# Microcontroller.net
KiCad netlist of a schematic drawn in Altium Designer
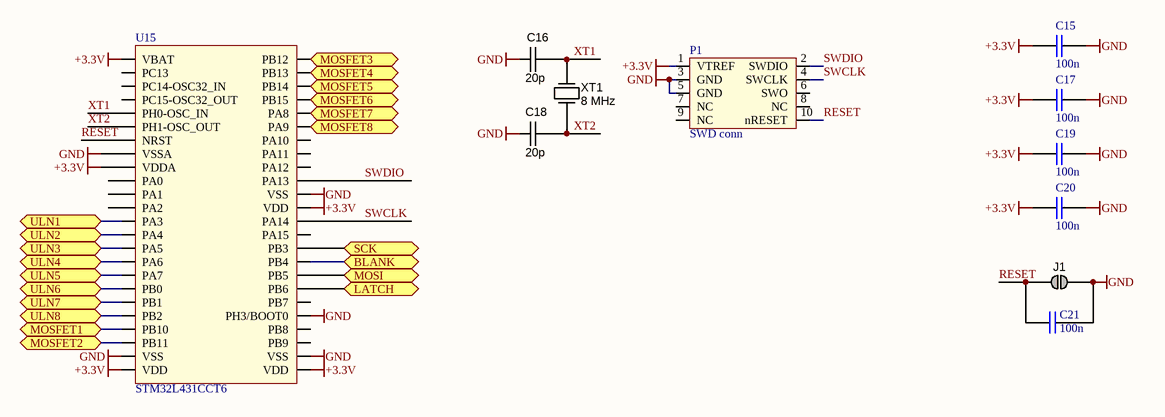
[diagram p0: Microcontroller.SchDoc]

(export (version "E")
  (design (tool "Eeschema 10.0.6"))
  (components
    (comp (ref "C15")
      (value "100n")
      (footprint "Cap 0603")
      (description "Capacitor 100nF 50V 0603 SMD")
      (libsource (lib "Komponente") (part "Cap 100nF 50V 0603 SMD"))
    )
    (comp (ref "C16")
      (value "20p")
      (footprint "CAPC2012X135N")
      (description "Capacitor SMD Cer 100nF 10% 50V X7R 0805")
      (fields (field (name "TOLERANCE") "±10%") (field (name "Comment") "approved sub OK"))
      (libsource (lib "PBL - Capacitors") (part "CAPC_100n_0805_X7R_50V_10%"))
    )
    (comp (ref "C17")
      (value "100n")
      (footprint "Cap 0603")
      (description "Capacitor 100nF 50V 0603 SMD")
      (libsource (lib "Komponente") (part "Cap 100nF 50V 0603 SMD"))
    )
    (comp (ref "C18")
      (value "20p")
      (footprint "CAPC2012X135N")
      (description "Capacitor SMD Cer 100nF 10% 50V X7R 0805")
      (fields (field (name "TOLERANCE") "±10%") (field (name "Comment") "approved sub OK"))
      (libsource (lib "PBL - Capacitors") (part "CAPC_100n_0805_X7R_50V_10%"))
    )
    (comp (ref "C19")
      (value "100n")
      (footprint "Cap 0603")
      (description "Capacitor 100nF 50V 0603 SMD")
      (libsource (lib "Komponente") (part "Cap 100nF 50V 0603 SMD"))
    )
    (comp (ref "C20")
      (value "100n")
      (footprint "Cap 0603")
      (description "Capacitor 100nF 50V 0603 SMD")
      (libsource (lib "Komponente") (part "Cap 100nF 50V 0603 SMD"))
    )
    (comp (ref "C21")
      (value "100n")
      (footprint "Cap 0603")
      (description "Capacitor 100nF 50V 0603 SMD")
      (libsource (lib "Komponente") (part "Cap 100nF 50V 0603 SMD"))
    )
    (comp (ref "J1")
      (value "Jumper")
      (footprint "HDR1X2")
      (description "SMD jumper")
      (libsource (lib "PBL - Pads and Jumpers") (part "JUMP1"))
    )
    (comp (ref "P1")
      (value "SWD conn")
      (footprint "SWD connector")
      (description "SWD connector")
      (libsource (lib "AltiumLibrary") (part "SW_debug"))
    )
    (comp (ref "U15")
      (value "STM32L431CCT6")
      (footprint "STM-LQFP48")
      (description "STM32 L4")
      (libsource (lib "Lib_darijo") (part "STM32L431CCT6"))
    )
    (comp (ref "XT1")
      (value "8 MHz")
      (footprint "CRYSTAL_HC49-US-SM")
      (description "Resonator Ceramic 6.00 MHz 30ppm")
      (libsource (lib "PBL - Resonators") (part "Crystal_6MHz_HC49/US"))
    )
  )
  (nets
    (net (code "1") (name "+3.3V") (class "Default")
      (node (ref "C15") (pin "1") (pinfunction "1_1") (pintype "passive"))
      (node (ref "C17") (pin "1") (pinfunction "1_1") (pintype "passive"))
      (node (ref "C19") (pin "1") (pinfunction "1_1") (pintype "passive"))
      (node (ref "C20") (pin "1") (pinfunction "1_1") (pintype "passive"))
      (node (ref "P1") (pin "1") (pinfunction "VTREF_1") (pintype "passive"))
      (node (ref "U15") (pin "1") (pinfunction "VBAT_1") (pintype "passive"))
      (node (ref "U15") (pin "24") (pinfunction "VDD_24") (pintype "passive"))
      (node (ref "U15") (pin "36") (pinfunction "VDD_36") (pintype "passive"))
      (node (ref "U15") (pin "48") (pinfunction "VDD_48") (pintype "passive"))
      (node (ref "U15") (pin "9") (pinfunction "VDDA_9") (pintype "passive"))
    )
    (net (code "2") (name "/BLANK") (class "Default")
      (node (ref "U15") (pin "40") (pinfunction "PB4_40") (pintype "passive"))
    )
    (net (code "3") (name "/LATCH") (class "Default")
      (node (ref "U15") (pin "42") (pinfunction "PB6_42") (pintype "passive"))
    )
    (net (code "4") (name "/MOSFET1") (class "Default")
      (node (ref "U15") (pin "21") (pinfunction "PB10_21") (pintype "passive"))
    )
    (net (code "5") (name "/MOSFET2") (class "Default")
      (node (ref "U15") (pin "22") (pinfunction "PB11_22") (pintype "passive"))
    )
    (net (code "6") (name "/MOSFET3") (class "Default")
      (node (ref "U15") (pin "25") (pinfunction "PB12_25") (pintype "passive"))
    )
    (net (code "7") (name "/MOSFET4") (class "Default")
      (node (ref "U15") (pin "26") (pinfunction "PB13_26") (pintype "passive"))
    )
    (net (code "8") (name "/MOSFET5") (class "Default")
      (node (ref "U15") (pin "27") (pinfunction "PB14_27") (pintype "passive"))
    )
    (net (code "9") (name "/MOSFET6") (class "Default")
      (node (ref "U15") (pin "28") (pinfunction "PB15_28") (pintype "passive"))
    )
    (net (code "10") (name "/MOSFET7") (class "Default")
      (node (ref "U15") (pin "29") (pinfunction "PA8_29") (pintype "passive"))
    )
    (net (code "11") (name "/MOSFET8") (class "Default")
      (node (ref "U15") (pin "30") (pinfunction "PA9_30") (pintype "passive"))
    )
    (net (code "12") (name "/MOSI") (class "Default")
      (node (ref "U15") (pin "41") (pinfunction "PB5_41") (pintype "passive"))
    )
    (net (code "13") (name "/RESET") (class "Default")
      (node (ref "C21") (pin "2") (pinfunction "2_2") (pintype "passive"))
      (node (ref "J1") (pin "1") (pintype "passive"))
      (node (ref "P1") (pin "10") (pinfunction "nRESET_10") (pintype "passive"))
      (node (ref "U15") (pin "7") (pinfunction "NRST_7") (pintype "passive"))
    )
    (net (code "14") (name "/SCK") (class "Default")
      (node (ref "U15") (pin "39") (pinfunction "PB3_39") (pintype "passive"))
    )
    (net (code "15") (name "/SWCLK") (class "Default")
      (node (ref "P1") (pin "4") (pinfunction "SWCLK_4") (pintype "passive"))
      (node (ref "U15") (pin "37") (pinfunction "PA14_37") (pintype "passive"))
    )
    (net (code "16") (name "/SWDIO") (class "Default")
      (node (ref "P1") (pin "2") (pinfunction "SWDIO_2") (pintype "passive"))
      (node (ref "U15") (pin "34") (pinfunction "PA13_34") (pintype "passive"))
    )
    (net (code "17") (name "/ULN1") (class "Default")
      (node (ref "U15") (pin "13") (pinfunction "PA3_13") (pintype "passive"))
    )
    (net (code "18") (name "/ULN2") (class "Default")
      (node (ref "U15") (pin "14") (pinfunction "PA4_14") (pintype "passive"))
    )
    (net (code "19") (name "/ULN3") (class "Default")
      (node (ref "U15") (pin "15") (pinfunction "PA5_15") (pintype "passive"))
    )
    (net (code "20") (name "/ULN4") (class "Default")
      (node (ref "U15") (pin "16") (pinfunction "PA6_16") (pintype "passive"))
    )
    (net (code "21") (name "/ULN5") (class "Default")
      (node (ref "U15") (pin "17") (pinfunction "PA7_17") (pintype "passive"))
    )
    (net (code "22") (name "/ULN6") (class "Default")
      (node (ref "U15") (pin "18") (pinfunction "PB0_18") (pintype "passive"))
    )
    (net (code "23") (name "/ULN7") (class "Default")
      (node (ref "U15") (pin "19") (pinfunction "PB1_19") (pintype "passive"))
    )
    (net (code "24") (name "/ULN8") (class "Default")
      (node (ref "U15") (pin "20") (pinfunction "PB2_20") (pintype "passive"))
    )
    (net (code "25") (name "/XT1") (class "Default")
      (node (ref "C16") (pin "1") (pintype "passive"))
      (node (ref "U15") (pin "5") (pinfunction "PH0-OSC_IN_5") (pintype "passive"))
      (node (ref "XT1") (pin "2") (pinfunction "OUT_2") (pintype "passive"))
    )
    (net (code "26") (name "/XT2") (class "Default")
      (node (ref "C18") (pin "1") (pintype "passive"))
      (node (ref "U15") (pin "6") (pinfunction "PH1-OSC_OUT_6") (pintype "passive"))
      (node (ref "XT1") (pin "1") (pinfunction "IN_1") (pintype "passive"))
    )
    (net (code "27") (name "GND") (class "Default")
      (node (ref "C15") (pin "2") (pinfunction "2_2") (pintype "passive"))
      (node (ref "C16") (pin "2") (pintype "passive"))
      (node (ref "C17") (pin "2") (pinfunction "2_2") (pintype "passive"))
      (node (ref "C18") (pin "2") (pintype "passive"))
      (node (ref "C19") (pin "2") (pinfunction "2_2") (pintype "passive"))
      (node (ref "C20") (pin "2") (pinfunction "2_2") (pintype "passive"))
      (node (ref "C21") (pin "1") (pinfunction "1_1") (pintype "passive"))
      (node (ref "J1") (pin "2") (pintype "passive"))
      (node (ref "P1") (pin "3") (pinfunction "GND_3") (pintype "passive"))
      (node (ref "P1") (pin "5") (pinfunction "GND_5") (pintype "passive"))
      (node (ref "U15") (pin "23") (pinfunction "VSS_23") (pintype "passive"))
      (node (ref "U15") (pin "35") (pinfunction "VSS_35") (pintype "passive"))
      (node (ref "U15") (pin "44") (pinfunction "PH3/BOOT0_44") (pintype "passive"))
      (node (ref "U15") (pin "47") (pinfunction "VSS_47") (pintype "passive"))
      (node (ref "U15") (pin "8") (pinfunction "VSSA_8") (pintype "passive"))
    )
    (net (code "28") (name "unconnected-(P1-NC-Pad7)") (class "Default")
      (node (ref "P1") (pin "7") (pinfunction "NC_7") (pintype "passive"))
    )
    (net (code "29") (name "unconnected-(P1-NC-Pad8)") (class "Default")
      (node (ref "P1") (pin "8") (pinfunction "NC_8") (pintype "passive"))
    )
    (net (code "30") (name "unconnected-(P1-NC-Pad9)") (class "Default")
      (node (ref "P1") (pin "9") (pinfunction "NC_9") (pintype "passive"))
    )
    (net (code "31") (name "unconnected-(P1-SWO-Pad6)") (class "Default")
      (node (ref "P1") (pin "6") (pinfunction "SWO_6") (pintype "passive"))
    )
    (net (code "32") (name "unconnected-(U15-PA0-Pad10)") (class "Default")
      (node (ref "U15") (pin "10") (pinfunction "PA0_10") (pintype "passive"))
    )
    (net (code "33") (name "unconnected-(U15-PA1-Pad11)") (class "Default")
      (node (ref "U15") (pin "11") (pinfunction "PA1_11") (pintype "passive"))
    )
    (net (code "34") (name "unconnected-(U15-PA2-Pad12)") (class "Default")
      (node (ref "U15") (pin "12") (pinfunction "PA2_12") (pintype "passive"))
    )
    (net (code "35") (name "unconnected-(U15-PA10-Pad31)") (class "Default")
      (node (ref "U15") (pin "31") (pinfunction "PA10_31") (pintype "passive"))
    )
    (net (code "36") (name "unconnected-(U15-PA11-Pad32)") (class "Default")
      (node (ref "U15") (pin "32") (pinfunction "PA11_32") (pintype "passive"))
    )
    (net (code "37") (name "unconnected-(U15-PA12-Pad33)") (class "Default")
      (node (ref "U15") (pin "33") (pinfunction "PA12_33") (pintype "passive"))
    )
    (net (code "38") (name "unconnected-(U15-PA15-Pad38)") (class "Default")
      (node (ref "U15") (pin "38") (pinfunction "PA15_38") (pintype "passive"))
    )
    (net (code "39") (name "unconnected-(U15-PB7-Pad43)") (class "Default")
      (node (ref "U15") (pin "43") (pinfunction "PB7_43") (pintype "passive"))
    )
    (net (code "40") (name "unconnected-(U15-PB8-Pad45)") (class "Default")
      (node (ref "U15") (pin "45") (pinfunction "PB8_45") (pintype "passive"))
    )
    (net (code "41") (name "unconnected-(U15-PB9-Pad46)") (class "Default")
      (node (ref "U15") (pin "46") (pinfunction "PB9_46") (pintype "passive"))
    )
    (net (code "42") (name "unconnected-(U15-PC13-Pad2)") (class "Default")
      (node (ref "U15") (pin "2") (pinfunction "PC13_2") (pintype "passive"))
    )
    (net (code "43") (name "unconnected-(U15-PC14-OSC32_IN-Pad3)") (class "Default")
      (node (ref "U15") (pin "3") (pinfunction "PC14-OSC32_IN_3") (pintype "passive"))
    )
    (net (code "44") (name "unconnected-(U15-PC15-OSC32_OUT-Pad4)") (class "Default")
      (node (ref "U15") (pin "4") (pinfunction "PC15-OSC32_OUT_4") (pintype "passive"))
    )
  )
)
